# Esquem_tico_1.net
KiCad netlist of a schematic drawn in EAGLE
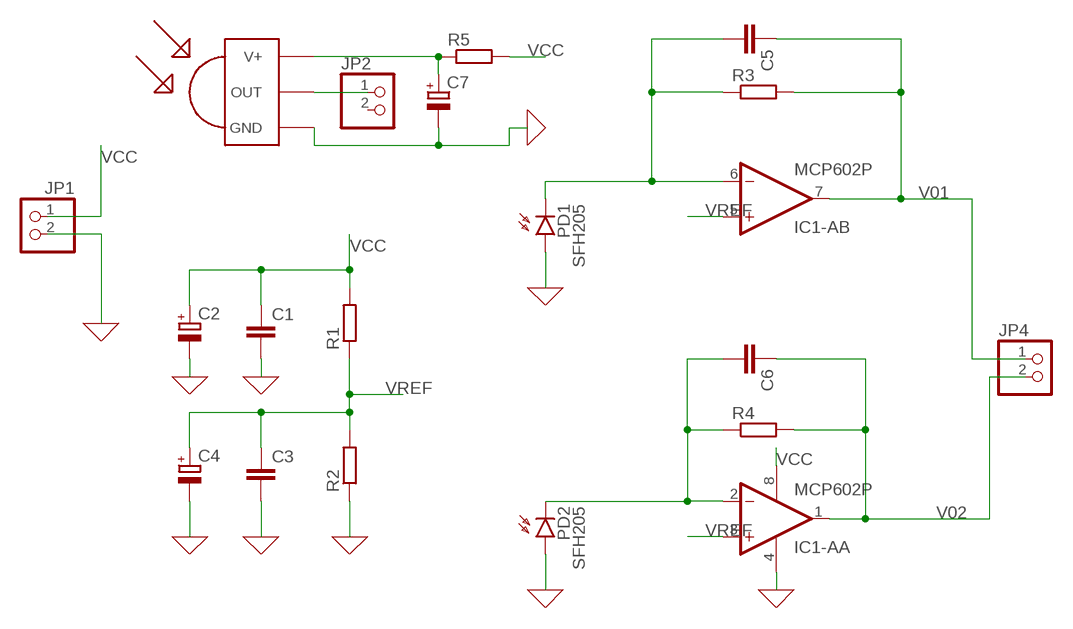
[diagram p0: schematic, sheet 1]

(export (version "E")
  (design (tool "Eeschema 10.0.6"))
  (components
    (comp (ref "C1")
      (value "C-EU025-025X050")
      (footprint "eagle-import:C025-025X050")
      (libsource (lib "eagle-import") (part "C-EU025-025X050"))
    )
    (comp (ref "C2")
      (value "CPOL-EUE2.5-6")
      (footprint "eagle-import:E2,5-6")
      (libsource (lib "eagle-import") (part "CPOL-EUE2.5-6"))
    )
    (comp (ref "C3")
      (value "C-EU025-025X050")
      (footprint "eagle-import:C025-025X050")
      (libsource (lib "eagle-import") (part "C-EU025-025X050"))
    )
    (comp (ref "C4")
      (value "CPOL-EUE2.5-6")
      (footprint "eagle-import:E2,5-6")
      (libsource (lib "eagle-import") (part "CPOL-EUE2.5-6"))
    )
    (comp (ref "C5")
      (value "C-EU025-025X050")
      (footprint "eagle-import:C025-025X050")
      (libsource (lib "eagle-import") (part "C-EU025-025X050"))
    )
    (comp (ref "C6")
      (value "C-EU025-025X050")
      (footprint "eagle-import:C025-025X050")
      (libsource (lib "eagle-import") (part "C-EU025-025X050"))
    )
    (comp (ref "C7")
      (value "CPOL-EUE2.5-6")
      (footprint "eagle-import:E2,5-6")
      (libsource (lib "eagle-import") (part "CPOL-EUE2.5-6"))
    )
    (comp (ref "IC1-A")
      (value "MCP602P")
      (footprint "eagle-import:DIL08")
      (libsource (lib "eagle-import") (part "MCP602P"))
    )
    (comp (ref "JP1")
      (value "PINHD-1X2")
      (footprint "eagle-import:1X02")
      (libsource (lib "eagle-import") (part "PINHD-1X2"))
    )
    (comp (ref "JP2")
      (value "PINHD-1X2")
      (footprint "eagle-import:1X02")
      (libsource (lib "eagle-import") (part "PINHD-1X2"))
    )
    (comp (ref "JP4")
      (value "PINHD-1X2")
      (footprint "eagle-import:1X02")
      (libsource (lib "eagle-import") (part "PINHD-1X2"))
    )
    (comp (ref "PD1")
      (value "SFH205")
      (footprint "eagle-import:SFH205")
      (libsource (lib "eagle-import") (part "SFH205"))
    )
    (comp (ref "PD2")
      (value "SFH205")
      (footprint "eagle-import:SFH205")
      (libsource (lib "eagle-import") (part "SFH205"))
    )
    (comp (ref "R1")
      (value "R-EU_0207/10")
      (footprint "eagle-import:0207_10")
      (libsource (lib "eagle-import") (part "R-EU_0207/10"))
    )
    (comp (ref "R2")
      (value "R-EU_0207/10")
      (footprint "eagle-import:0207_10")
      (libsource (lib "eagle-import") (part "R-EU_0207/10"))
    )
    (comp (ref "R3")
      (value "R-EU_0207/10")
      (footprint "eagle-import:0207_10")
      (libsource (lib "eagle-import") (part "R-EU_0207/10"))
    )
    (comp (ref "R4")
      (value "R-EU_0207/10")
      (footprint "eagle-import:0207_10")
      (libsource (lib "eagle-import") (part "R-EU_0207/10"))
    )
    (comp (ref "R5")
      (value "R-EU_0207/10")
      (footprint "eagle-import:0207_10")
      (libsource (lib "eagle-import") (part "R-EU_0207/10"))
    )
    (comp (ref "U$1")
      (value "TSOP4856")
      (footprint "eagle-import:TSOP18XX")
      (libsource (lib "eagle-import") (part "TSOP4856"))
    )
  )
  (nets
    (net (code "1") (name "/V01") (class "Default")
      (node (ref "C5") (pin "1") (pinfunction "1_1") (pintype "passive"))
      (node (ref "IC1-A") (pin "7") (pinfunction "OUT_7") (pintype "output"))
      (node (ref "JP4") (pin "1") (pinfunction "1_1") (pintype "passive"))
      (node (ref "R3") (pin "2") (pinfunction "2_2") (pintype "passive"))
    )
    (net (code "2") (name "/V02") (class "Default")
      (node (ref "C6") (pin "1") (pinfunction "1_1") (pintype "passive"))
      (node (ref "IC1-A") (pin "1") (pinfunction "OUT_1") (pintype "output"))
      (node (ref "JP4") (pin "2") (pinfunction "2_2") (pintype "passive"))
      (node (ref "R4") (pin "2") (pinfunction "2_2") (pintype "passive"))
    )
    (net (code "3") (name "/VCC") (class "Default")
      (node (ref "C1") (pin "1") (pinfunction "1_1") (pintype "passive"))
      (node (ref "C2") (pin "+") (pinfunction "+_+") (pintype "passive"))
      (node (ref "IC1-A") (pin "8") (pinfunction "V+_8") (pintype "power_in"))
      (node (ref "JP1") (pin "1") (pinfunction "1_1") (pintype "passive"))
      (node (ref "R1") (pin "2") (pinfunction "2_2") (pintype "passive"))
      (node (ref "R5") (pin "2") (pinfunction "2_2") (pintype "passive"))
    )
    (net (code "4") (name "/VREF") (class "Default")
      (node (ref "C3") (pin "1") (pinfunction "1_1") (pintype "passive"))
      (node (ref "C4") (pin "+") (pinfunction "+_+") (pintype "passive"))
      (node (ref "IC1-A") (pin "3") (pinfunction "+IN_3") (pintype "input"))
      (node (ref "IC1-A") (pin "5") (pinfunction "+IN_5") (pintype "input"))
      (node (ref "R1") (pin "1") (pinfunction "1_1") (pintype "passive"))
      (node (ref "R2") (pin "2") (pinfunction "2_2") (pintype "passive"))
    )
    (net (code "5") (name "GND") (class "Default")
      (node (ref "C1") (pin "2") (pinfunction "2_2") (pintype "passive"))
      (node (ref "C2") (pin "-") (pinfunction "-_-") (pintype "passive"))
      (node (ref "C3") (pin "2") (pinfunction "2_2") (pintype "passive"))
      (node (ref "C4") (pin "-") (pinfunction "-_-") (pintype "passive"))
      (node (ref "C7") (pin "-") (pinfunction "-_-") (pintype "passive"))
      (node (ref "IC1-A") (pin "4") (pinfunction "V-_4") (pintype "power_in"))
      (node (ref "JP1") (pin "2") (pinfunction "2_2") (pintype "passive"))
      (node (ref "PD1") (pin "A") (pinfunction "A_A") (pintype "passive"))
      (node (ref "PD2") (pin "A") (pinfunction "A_A") (pintype "passive"))
      (node (ref "R2") (pin "1") (pinfunction "1_1") (pintype "passive"))
      (node (ref "U$1") (pin "GND") (pinfunction "GND_GND") (pintype "bidirectional"))
    )
    (net (code "6") (name "Net-(IC1-AA--IN)") (class "Default")
      (node (ref "C6") (pin "2") (pinfunction "2_2") (pintype "passive"))
      (node (ref "IC1-A") (pin "2") (pinfunction "-IN_2") (pintype "input"))
      (node (ref "PD2") (pin "K") (pinfunction "C_K") (pintype "passive"))
      (node (ref "R4") (pin "1") (pinfunction "1_1") (pintype "passive"))
    )
    (net (code "7") (name "Net-(IC1-AB--IN)") (class "Default")
      (node (ref "C5") (pin "2") (pinfunction "2_2") (pintype "passive"))
      (node (ref "IC1-A") (pin "6") (pinfunction "-IN_6") (pintype "input"))
      (node (ref "PD1") (pin "K") (pinfunction "C_K") (pintype "passive"))
      (node (ref "R3") (pin "1") (pinfunction "1_1") (pintype "passive"))
    )
    (net (code "8") (name "Net-(JP2-Pad1)") (class "Default")
      (node (ref "JP2") (pin "1") (pinfunction "1_1") (pintype "passive"))
      (node (ref "U$1") (pin "OUT") (pinfunction "OUT_OUT") (pintype "bidirectional"))
    )
    (net (code "9") (name "Net-(U$1-V+)") (class "Default")
      (node (ref "C7") (pin "+") (pinfunction "+_+") (pintype "passive"))
      (node (ref "R5") (pin "1") (pinfunction "1_1") (pintype "passive"))
      (node (ref "U$1") (pin "VCC") (pinfunction "V+_VCC") (pintype "bidirectional"))
    )
    (net (code "10") (name "unconnected-(JP2-Pad2)") (class "Default")
      (node (ref "JP2") (pin "2") (pinfunction "2_2") (pintype "passive"))
    )
  )
)
